# uc4h_node_v2010.net
KiCad netlist of a schematic drawn in EAGLE
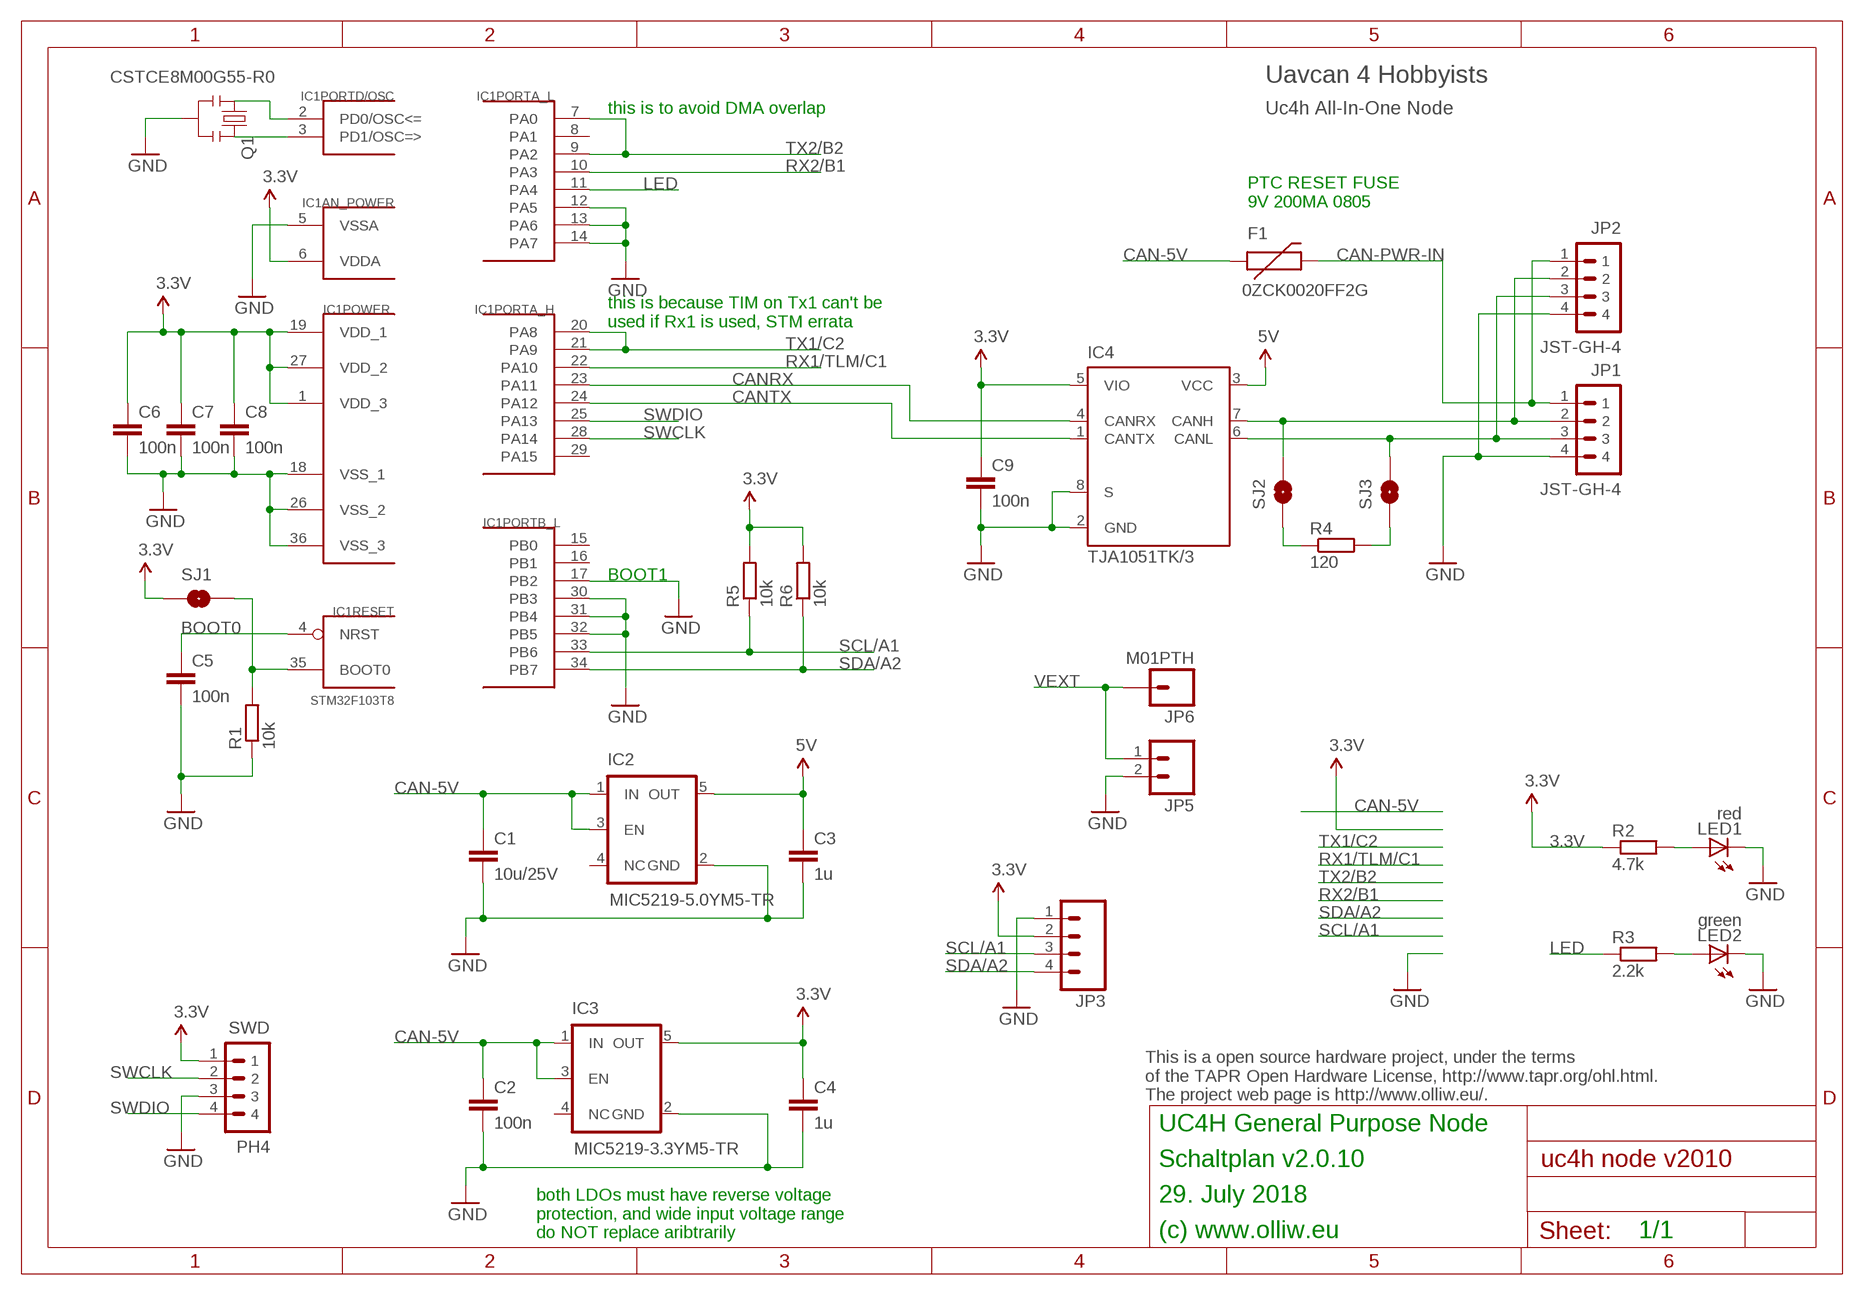
[diagram p0: schematic, sheet 1]

(export (version "E")
  (design (tool "Eeschema 10.0.6"))
  (components
    (comp (ref "C1")
      (value "10u/25V")
      (footprint "eagle-import:C1206")
      (libsource (lib "eagle-import") (part "C-EUC1206"))
    )
    (comp (ref "C2")
      (value "100n")
      (footprint "eagle-import:C0603K")
      (libsource (lib "eagle-import") (part "C-EUC0603K"))
    )
    (comp (ref "C3")
      (value "1u")
      (footprint "eagle-import:C0603K")
      (libsource (lib "eagle-import") (part "C-EUC0603K"))
    )
    (comp (ref "C4")
      (value "1u")
      (footprint "eagle-import:C0603K")
      (libsource (lib "eagle-import") (part "C-EUC0603K"))
    )
    (comp (ref "C5")
      (value "100n")
      (footprint "eagle-import:C0603K")
      (libsource (lib "eagle-import") (part "C-EUC0603K"))
    )
    (comp (ref "C6")
      (value "100n")
      (footprint "eagle-import:C0603K")
      (libsource (lib "eagle-import") (part "C-EUC0603K"))
    )
    (comp (ref "C7")
      (value "100n")
      (footprint "eagle-import:C0603K")
      (libsource (lib "eagle-import") (part "C-EUC0603K"))
    )
    (comp (ref "C8")
      (value "100n")
      (footprint "eagle-import:C0603K")
      (libsource (lib "eagle-import") (part "C-EUC0603K"))
    )
    (comp (ref "C9")
      (value "100n")
      (footprint "eagle-import:C0603K")
      (libsource (lib "eagle-import") (part "C-EUC0603K"))
    )
    (comp (ref "F1")
      (value "0ZCK0020FF2G")
      (footprint "eagle-import:FUSE-0805")
      (libsource (lib "eagle-import") (part "FUSE-PTCFUSE-0805"))
    )
    (comp (ref "IC1")
      (value "STM32F103T8")
      (footprint "eagle-import:VFQFPN36")
      (libsource (lib "eagle-import") (part "STM32F10XTXU6"))
    )
    (comp (ref "IC2")
      (value "MIC5219-5.0YM5-TR")
      (footprint "eagle-import:SOT23-5")
      (libsource (lib "eagle-import") (part "V_REG_TPS76433SOT23-5"))
    )
    (comp (ref "IC3")
      (value "MIC5219-3.3YM5-TR")
      (footprint "eagle-import:SOT23-5")
      (libsource (lib "eagle-import") (part "V_REG_TPS76433SOT23-5"))
    )
    (comp (ref "IC4")
      (value "TJA1051TK/3")
      (footprint "eagle-import:HVSON8")
      (libsource (lib "eagle-import") (part "TJA1051TK/3"))
    )
    (comp (ref "JP1")
      (value "JST-GH-4")
      (footprint "eagle-import:SM04B-GHS-TB")
      (libsource (lib "eagle-import") (part "JST-GH-4"))
    )
    (comp (ref "JP2")
      (value "JST-GH-4")
      (footprint "eagle-import:SM04B-GHS-TB")
      (libsource (lib "eagle-import") (part "JST-GH-4"))
    )
    (comp (ref "JP3")
      (value "M04PTH")
      (footprint "eagle-import:1X04")
      (libsource (lib "eagle-import") (part "M04PTH"))
    )
    (comp (ref "JP5")
      (value "M02PTH")
      (footprint "eagle-import:1X02")
      (libsource (lib "eagle-import") (part "M02PTH"))
    )
    (comp (ref "JP6")
      (value "M01PTH")
      (footprint "eagle-import:1X01")
      (libsource (lib "eagle-import") (part "M01PTH"))
    )
    (comp (ref "LED1")
      (value "red")
      (footprint "eagle-import:CHIPLED_0603")
      (libsource (lib "eagle-import") (part "LEDCHIPLED_0603"))
    )
    (comp (ref "LED2")
      (value "green")
      (footprint "eagle-import:CHIPLED_0603")
      (libsource (lib "eagle-import") (part "LEDCHIPLED_0603"))
    )
    (comp (ref "Q1")
      (value "CSTCE8M00G55-R0")
      (footprint "eagle-import:RESONATOR-SMD")
      (libsource (lib "eagle-import") (part "RESONATORSMD"))
    )
    (comp (ref "R1")
      (value "10k")
      (footprint "eagle-import:R0603")
      (libsource (lib "eagle-import") (part "R-EU_R0603"))
    )
    (comp (ref "R2")
      (value "4.7k")
      (footprint "eagle-import:R0603")
      (libsource (lib "eagle-import") (part "R-EU_R0603"))
    )
    (comp (ref "R3")
      (value "2.2k")
      (footprint "eagle-import:R0603")
      (libsource (lib "eagle-import") (part "R-EU_R0603"))
    )
    (comp (ref "R4")
      (value "120")
      (footprint "eagle-import:R0603")
      (libsource (lib "eagle-import") (part "R-EU_R0603"))
    )
    (comp (ref "R5")
      (value "10k")
      (footprint "eagle-import:R0603")
      (libsource (lib "eagle-import") (part "R-EU_R0603"))
    )
    (comp (ref "R6")
      (value "10k")
      (footprint "eagle-import:R0603")
      (libsource (lib "eagle-import") (part "R-EU_R0603"))
    )
    (comp (ref "SJ1")
      (value "BOOT0")
      (footprint "eagle-import:SJ_2S-NO")
      (libsource (lib "eagle-import") (part "SOLDERJUMPERNO"))
    )
    (comp (ref "SJ2")
      (value "SOLDERJUMPERNO")
      (footprint "eagle-import:SJ_2S-NO")
      (libsource (lib "eagle-import") (part "SOLDERJUMPERNO"))
    )
    (comp (ref "SJ3")
      (value "SOLDERJUMPERNO")
      (footprint "eagle-import:SJ_2S-NO")
      (libsource (lib "eagle-import") (part "SOLDERJUMPERNO"))
    )
    (comp (ref "SWD")
      (value "PH4")
      (footprint "eagle-import:4X1_1P27_OCT_BILEX")
      (libsource (lib "eagle-import") (part "P4X1_1P27-OCT_BILEX"))
    )
  )
  (nets
    (net (code "1") (name "/CAN-5V") (class "Default")
      (node (ref "C1") (pin "1") (pinfunction "1_1") (pintype "passive"))
      (node (ref "C2") (pin "1") (pinfunction "1_1") (pintype "passive"))
      (node (ref "F1") (pin "1") (pinfunction "1_1") (pintype "bidirectional"))
      (node (ref "IC2") (pin "1") (pinfunction "IN_1") (pintype "power_in"))
      (node (ref "IC2") (pin "3") (pinfunction "EN_3") (pintype "input"))
      (node (ref "IC3") (pin "1") (pinfunction "IN_1") (pintype "power_in"))
      (node (ref "IC3") (pin "3") (pinfunction "EN_3") (pintype "input"))
    )
    (net (code "2") (name "/CAN-PWR-IN") (class "Default")
      (node (ref "F1") (pin "2") (pinfunction "2_2") (pintype "bidirectional"))
      (node (ref "JP1") (pin "1") (pinfunction "1_1") (pintype "passive"))
      (node (ref "JP2") (pin "1") (pinfunction "1_1") (pintype "passive"))
    )
    (net (code "3") (name "/CANRX") (class "Default")
      (node (ref "IC1") (pin "23") (pinfunction "PA11_23") (pintype "bidirectional"))
      (node (ref "IC4") (pin "4") (pinfunction "CANRX_4") (pintype "output"))
    )
    (net (code "4") (name "/CANTX") (class "Default")
      (node (ref "IC1") (pin "24") (pinfunction "PA12_24") (pintype "bidirectional"))
      (node (ref "IC4") (pin "1") (pinfunction "CANTX_1") (pintype "input"))
    )
    (net (code "5") (name "/LED") (class "Default")
      (node (ref "IC1") (pin "11") (pinfunction "PA4_11") (pintype "bidirectional"))
      (node (ref "R3") (pin "1") (pinfunction "1_1") (pintype "passive"))
    )
    (net (code "6") (name "/RX1{slash}TLM{slash}C1") (class "Default")
      (node (ref "IC1") (pin "22") (pinfunction "PA10_22") (pintype "bidirectional"))
    )
    (net (code "7") (name "/RX2{slash}B1") (class "Default")
      (node (ref "IC1") (pin "10") (pinfunction "PA3_10") (pintype "bidirectional"))
    )
    (net (code "8") (name "/SCL{slash}A1") (class "Default")
      (node (ref "IC1") (pin "33") (pinfunction "PB6_33") (pintype "bidirectional"))
      (node (ref "JP3") (pin "3") (pinfunction "3_3") (pintype "passive"))
      (node (ref "R5") (pin "1") (pinfunction "1_1") (pintype "passive"))
    )
    (net (code "9") (name "/SDA{slash}A2") (class "Default")
      (node (ref "IC1") (pin "34") (pinfunction "PB7_34") (pintype "bidirectional"))
      (node (ref "JP3") (pin "4") (pinfunction "4_4") (pintype "passive"))
      (node (ref "R6") (pin "1") (pinfunction "1_1") (pintype "passive"))
    )
    (net (code "10") (name "/SWCLK") (class "Default")
      (node (ref "IC1") (pin "28") (pinfunction "PA14_28") (pintype "bidirectional"))
      (node (ref "SWD") (pin "2") (pinfunction "2_2") (pintype "passive"))
    )
    (net (code "11") (name "/SWDIO") (class "Default")
      (node (ref "IC1") (pin "25") (pinfunction "PA13_25") (pintype "bidirectional"))
      (node (ref "SWD") (pin "4") (pinfunction "4_4") (pintype "passive"))
    )
    (net (code "12") (name "/TX1{slash}C2") (class "Default")
      (node (ref "IC1") (pin "20") (pinfunction "PA8_20") (pintype "bidirectional"))
      (node (ref "IC1") (pin "21") (pinfunction "PA9_21") (pintype "bidirectional"))
    )
    (net (code "13") (name "/TX2{slash}B2") (class "Default")
      (node (ref "IC1") (pin "7") (pinfunction "PA0_7") (pintype "bidirectional"))
      (node (ref "IC1") (pin "9") (pinfunction "PA2_9") (pintype "bidirectional"))
    )
    (net (code "14") (name "/VEXT") (class "Default")
      (node (ref "JP5") (pin "1") (pinfunction "1_1") (pintype "passive"))
      (node (ref "JP6") (pin "1") (pinfunction "1_1") (pintype "passive"))
    )
    (net (code "15") (name "3.3V") (class "Default")
      (node (ref "C4") (pin "1") (pinfunction "1_1") (pintype "passive"))
      (node (ref "C6") (pin "1") (pinfunction "1_1") (pintype "passive"))
      (node (ref "C7") (pin "1") (pinfunction "1_1") (pintype "passive"))
      (node (ref "C8") (pin "1") (pinfunction "1_1") (pintype "passive"))
      (node (ref "C9") (pin "1") (pinfunction "1_1") (pintype "passive"))
      (node (ref "IC1") (pin "1") (pinfunction "VDD_3_1") (pintype "power_in"))
      (node (ref "IC1") (pin "19") (pinfunction "VDD_1_19") (pintype "power_in"))
      (node (ref "IC1") (pin "27") (pinfunction "VDD_2_27") (pintype "power_in"))
      (node (ref "IC1") (pin "6") (pinfunction "VDDA_6") (pintype "power_in"))
      (node (ref "IC3") (pin "5") (pinfunction "OUT_5") (pintype "output"))
      (node (ref "IC4") (pin "5") (pinfunction "VIO_5") (pintype "power_in"))
      (node (ref "JP3") (pin "2") (pinfunction "2_2") (pintype "passive"))
      (node (ref "R2") (pin "1") (pinfunction "1_1") (pintype "passive"))
      (node (ref "R5") (pin "2") (pinfunction "2_2") (pintype "passive"))
      (node (ref "R6") (pin "2") (pinfunction "2_2") (pintype "passive"))
      (node (ref "SJ1") (pin "1") (pinfunction "1_1") (pintype "passive"))
      (node (ref "SWD") (pin "1") (pinfunction "1_1") (pintype "passive"))
    )
    (net (code "16") (name "5V") (class "Default")
      (node (ref "C3") (pin "1") (pinfunction "1_1") (pintype "passive"))
      (node (ref "IC2") (pin "5") (pinfunction "OUT_5") (pintype "output"))
      (node (ref "IC4") (pin "3") (pinfunction "VCC_3") (pintype "power_in"))
    )
    (net (code "17") (name "GND") (class "Default")
      (node (ref "C1") (pin "2") (pinfunction "2_2") (pintype "passive"))
      (node (ref "C2") (pin "2") (pinfunction "2_2") (pintype "passive"))
      (node (ref "C3") (pin "2") (pinfunction "2_2") (pintype "passive"))
      (node (ref "C4") (pin "2") (pinfunction "2_2") (pintype "passive"))
      (node (ref "C5") (pin "2") (pinfunction "2_2") (pintype "passive"))
      (node (ref "C6") (pin "2") (pinfunction "2_2") (pintype "passive"))
      (node (ref "C7") (pin "2") (pinfunction "2_2") (pintype "passive"))
      (node (ref "C8") (pin "2") (pinfunction "2_2") (pintype "passive"))
      (node (ref "C9") (pin "2") (pinfunction "2_2") (pintype "passive"))
      (node (ref "IC1") (pin "12") (pinfunction "PA5_12") (pintype "bidirectional"))
      (node (ref "IC1") (pin "13") (pinfunction "PA6_13") (pintype "bidirectional"))
      (node (ref "IC1") (pin "14") (pinfunction "PA7_14") (pintype "bidirectional"))
      (node (ref "IC1") (pin "17") (pinfunction "PB2_17") (pintype "bidirectional"))
      (node (ref "IC1") (pin "18") (pinfunction "VSS_1_18") (pintype "power_in"))
      (node (ref "IC1") (pin "26") (pinfunction "VSS_2_26") (pintype "power_in"))
      (node (ref "IC1") (pin "30") (pinfunction "PB3_30") (pintype "bidirectional"))
      (node (ref "IC1") (pin "31") (pinfunction "PB4_31") (pintype "bidirectional"))
      (node (ref "IC1") (pin "32") (pinfunction "PB5_32") (pintype "bidirectional"))
      (node (ref "IC1") (pin "36") (pinfunction "VSS_3_36") (pintype "power_in"))
      (node (ref "IC1") (pin "5") (pinfunction "VSSA_5") (pintype "power_in"))
      (node (ref "IC2") (pin "2") (pinfunction "GND_2") (pintype "power_in"))
      (node (ref "IC3") (pin "2") (pinfunction "GND_2") (pintype "power_in"))
      (node (ref "IC4") (pin "2") (pinfunction "GND_2") (pintype "power_in"))
      (node (ref "IC4") (pin "8") (pinfunction "S_8") (pintype "input"))
      (node (ref "JP1") (pin "4") (pinfunction "4_4") (pintype "passive"))
      (node (ref "JP2") (pin "4") (pinfunction "4_4") (pintype "passive"))
      (node (ref "JP3") (pin "1") (pinfunction "1_1") (pintype "passive"))
      (node (ref "JP5") (pin "2") (pinfunction "2_2") (pintype "passive"))
      (node (ref "LED1") (pin "C") (pinfunction "C_C") (pintype "passive"))
      (node (ref "LED2") (pin "C") (pinfunction "C_C") (pintype "passive"))
      (node (ref "Q1") (pin "2") (pinfunction "2_2") (pintype "passive"))
      (node (ref "R1") (pin "1") (pinfunction "1_1") (pintype "passive"))
      (node (ref "SWD") (pin "3") (pinfunction "3_3") (pintype "passive"))
    )
    (net (code "18") (name "Net-(IC1E-PD0{slash}OSC<=)") (class "Default")
      (node (ref "IC1") (pin "2") (pinfunction "PD0/OSC<=_2") (pintype "bidirectional"))
      (node (ref "Q1") (pin "1") (pinfunction "1_1") (pintype "passive"))
    )
    (net (code "19") (name "Net-(IC1E-PD1{slash}OSC=>)") (class "Default")
      (node (ref "IC1") (pin "3") (pinfunction "PD1/OSC=>_3") (pintype "bidirectional"))
      (node (ref "Q1") (pin "3") (pinfunction "3_3") (pintype "passive"))
    )
    (net (code "20") (name "Net-(IC1G-BOOT0)") (class "Default")
      (node (ref "IC1") (pin "35") (pinfunction "BOOT0_35") (pintype "input"))
      (node (ref "R1") (pin "2") (pinfunction "2_2") (pintype "passive"))
      (node (ref "SJ1") (pin "2") (pinfunction "2_2") (pintype "passive"))
    )
    (net (code "21") (name "Net-(IC1G-NRST)") (class "Default")
      (node (ref "C5") (pin "1") (pinfunction "1_1") (pintype "passive"))
      (node (ref "IC1") (pin "4") (pinfunction "NRST_4") (pintype "input"))
    )
    (net (code "22") (name "Net-(IC4-CANH)") (class "Default")
      (node (ref "IC4") (pin "7") (pinfunction "CANH_7") (pintype "bidirectional"))
      (node (ref "JP1") (pin "2") (pinfunction "2_2") (pintype "passive"))
      (node (ref "JP2") (pin "2") (pinfunction "2_2") (pintype "passive"))
      (node (ref "SJ2") (pin "2") (pinfunction "2_2") (pintype "passive"))
    )
    (net (code "23") (name "Net-(IC4-CANL)") (class "Default")
      (node (ref "IC4") (pin "6") (pinfunction "CANL_6") (pintype "bidirectional"))
      (node (ref "JP1") (pin "3") (pinfunction "3_3") (pintype "passive"))
      (node (ref "JP2") (pin "3") (pinfunction "3_3") (pintype "passive"))
      (node (ref "SJ3") (pin "2") (pinfunction "2_2") (pintype "passive"))
    )
    (net (code "24") (name "Net-(LED1-PadA)") (class "Default")
      (node (ref "LED1") (pin "A") (pinfunction "A_A") (pintype "passive"))
      (node (ref "R2") (pin "2") (pinfunction "2_2") (pintype "passive"))
    )
    (net (code "25") (name "Net-(LED2-PadA)") (class "Default")
      (node (ref "LED2") (pin "A") (pinfunction "A_A") (pintype "passive"))
      (node (ref "R3") (pin "2") (pinfunction "2_2") (pintype "passive"))
    )
    (net (code "26") (name "Net-(R4-Pad1)") (class "Default")
      (node (ref "R4") (pin "1") (pinfunction "1_1") (pintype "passive"))
      (node (ref "SJ2") (pin "1") (pinfunction "1_1") (pintype "passive"))
    )
    (net (code "27") (name "Net-(R4-Pad2)") (class "Default")
      (node (ref "R4") (pin "2") (pinfunction "2_2") (pintype "passive"))
      (node (ref "SJ3") (pin "1") (pinfunction "1_1") (pintype "passive"))
    )
    (net (code "28") (name "unconnected-(IC1B-PA15-Pad29)") (class "Default")
      (node (ref "IC1") (pin "29") (pinfunction "PA15_29") (pintype "bidirectional"))
    )
    (net (code "29") (name "unconnected-(IC1C-PA1-Pad8)") (class "Default")
      (node (ref "IC1") (pin "8") (pinfunction "PA1_8") (pintype "bidirectional"))
    )
    (net (code "30") (name "unconnected-(IC1D-PB0-Pad15)") (class "Default")
      (node (ref "IC1") (pin "15") (pinfunction "PB0_15") (pintype "bidirectional"))
    )
    (net (code "31") (name "unconnected-(IC1D-PB1-Pad16)") (class "Default")
      (node (ref "IC1") (pin "16") (pinfunction "PB1_16") (pintype "bidirectional"))
    )
    (net (code "32") (name "unconnected-(IC2-NC-Pad4)") (class "Default")
      (node (ref "IC2") (pin "4") (pinfunction "NC_4") (pintype "passive"))
    )
    (net (code "33") (name "unconnected-(IC3-NC-Pad4)") (class "Default")
      (node (ref "IC3") (pin "4") (pinfunction "NC_4") (pintype "passive"))
    )
  )
)
